# Input_Protection.net
KiCad netlist of a schematic drawn in Altium Designer
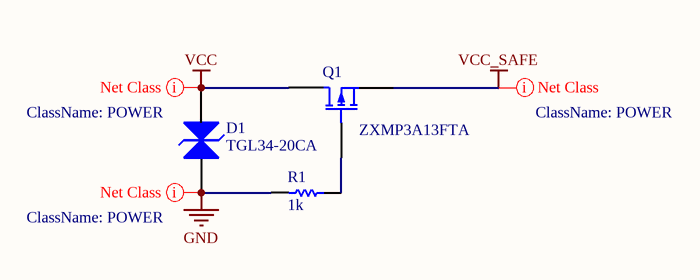
[diagram p0: Input Protection.SchDoc]

(export (version "E")
  (design (tool "Eeschema 10.0.6"))
  (components
    (comp (ref "D1")
      (value "TGL34-20CA")
      (footprint "DIO_MELF_IPC_MD")
      (description "Transil")
      (libsource (lib "agh_racing_2018") (part "TGL34-20CA"))
    )
    (comp (ref "Q1")
      (value "ZXMP3A13FTA")
      (footprint "SOT23_IPC_MD")
      (description "P-mosfet")
      (libsource (lib "agh_racing_2018") (part "ZXMP3A13FTA"))
    )
    (comp (ref "R1")
      (value "1k")
      (footprint "agh_racing_2018:RES_0603_IPC_HD")
      (description "Resistor")
      (fields (field (name "Comment") "Res"))
      (libsource (lib "agh_racing_2018") (part "Res"))
    )
  )
  (nets
    (net (code "1") (name "GND") (class "Default")
      (node (ref "D1") (pin "1") (pinfunction "IN1_1") (pintype "passive"))
      (node (ref "R1") (pin "2") (pinfunction "2_2") (pintype "passive"))
    )
    (net (code "2") (name "Net-(Q1-G)") (class "Default")
      (node (ref "Q1") (pin "1") (pinfunction "G_1") (pintype "passive"))
      (node (ref "R1") (pin "1") (pinfunction "1_1") (pintype "passive"))
    )
    (net (code "3") (name "VCC") (class "Default")
      (node (ref "D1") (pin "2") (pinfunction "IN2_2") (pintype "passive"))
      (node (ref "Q1") (pin "3") (pinfunction "D_3") (pintype "passive"))
    )
    (net (code "4") (name "VCC_SAFE") (class "Default")
      (node (ref "Q1") (pin "2") (pinfunction "S_2") (pintype "passive"))
    )
  )
)
